# 2-FrontEnd.net
KiCad netlist of a schematic drawn in Altium Designer
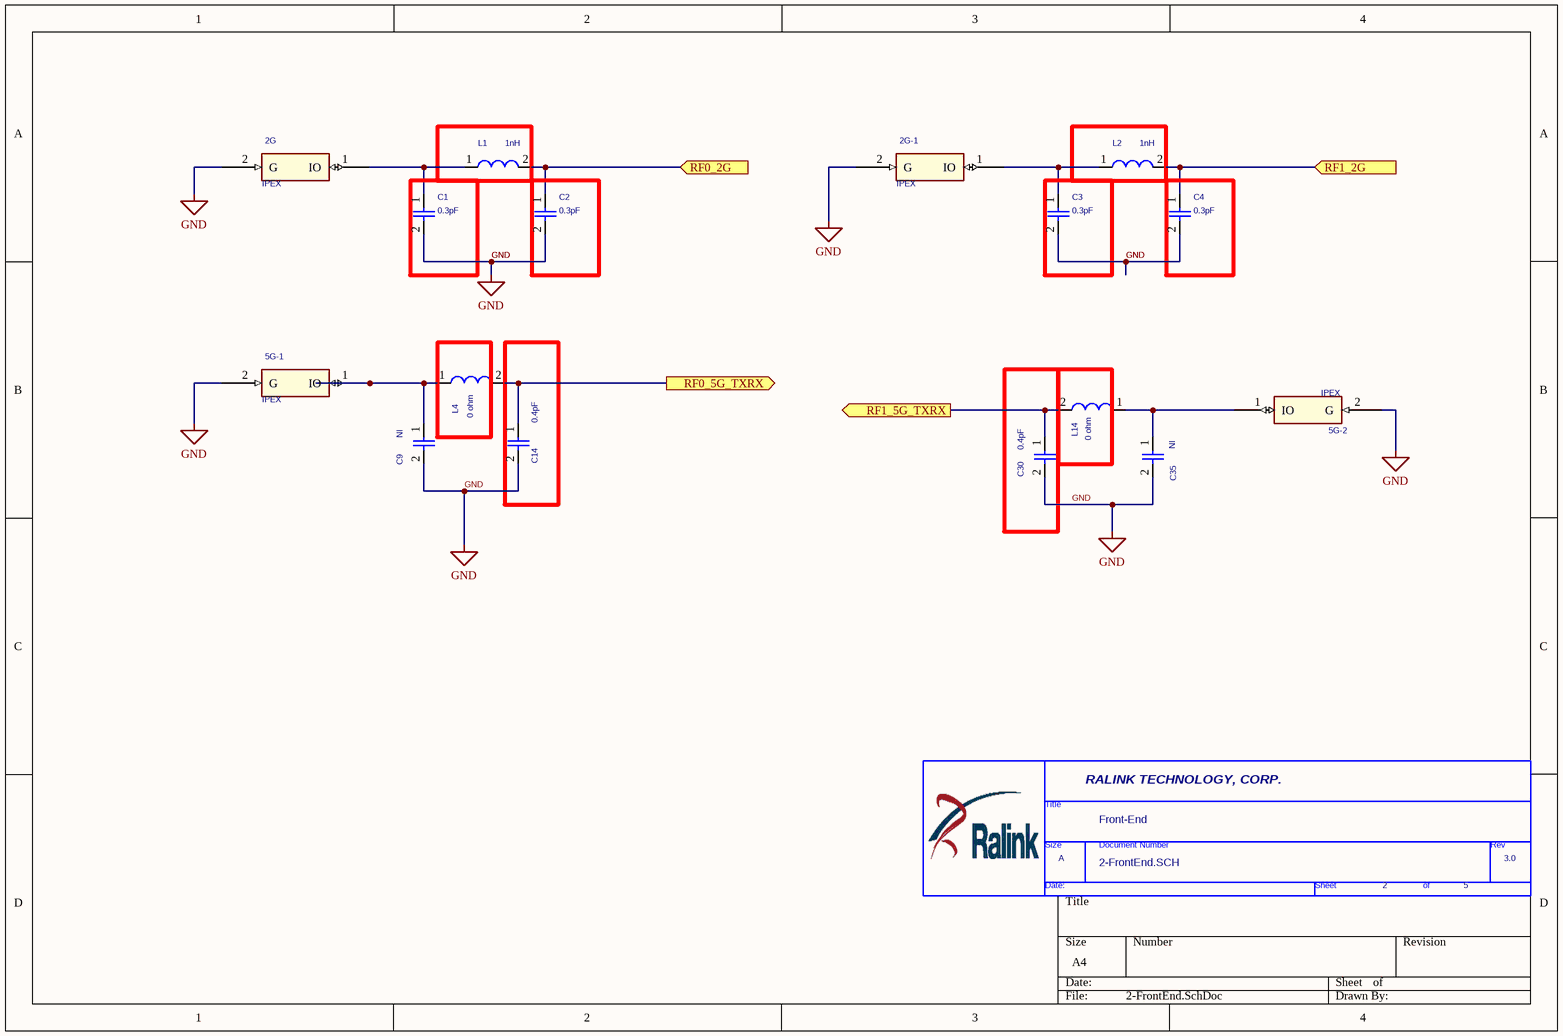
[diagram p0: 2-FrontEnd.SchDoc]

(export (version "E")
  (design (tool "Eeschema 10.0.6"))
  (components
    (comp (ref "2G") (value "IPEX") (footprint "IPEX") (libsource (lib "*") (part "ANT-RA-USB-1")))
    (comp (ref "2G-1") (value "IPEX") (footprint "IPEX") (libsource (lib "*") (part "ANT-RA-USB-1")))
    (comp (ref "5G-1") (value "IPEX") (footprint "IPEX") (libsource (lib "*") (part "ANT-RA-USB-1")))
    (comp (ref "5G-2") (value "IPEX") (footprint "IPEX") (libsource (lib "") (part "ANT-RA-USB-1_1")))
    (comp (ref "C1") (value "0.3pF") (footprint "0402") (libsource (lib "*") (part "CAP/0402")))
    (comp (ref "C2") (value "0.3pF") (footprint "0402") (libsource (lib "*") (part "CAP/0402")))
    (comp (ref "C3") (value "0.3pF") (footprint "0402") (libsource (lib "*") (part "CAP/0402")))
    (comp (ref "C4") (value "0.3pF") (footprint "0402") (libsource (lib "*") (part "CAP/0402")))
    (comp (ref "C9") (value "NI") (footprint "0402") (libsource (lib "*") (part "CAP/0402")))
    (comp (ref "C14") (value "0.4pF") (footprint "0402") (libsource (lib "*") (part "CAP/0402")))
    (comp (ref "C30") (value "0.4pF") (footprint "0402") (libsource (lib "*") (part "CAP/0402")))
    (comp (ref "C35") (value "NI") (footprint "0402") (libsource (lib "*") (part "CAP/0402")))
    (comp (ref "L1") (value "1nH") (footprint "0402") (libsource (lib "*") (part "L/0402")))
    (comp (ref "L2") (value "1nH") (footprint "0402") (libsource (lib "*") (part "L/0402")))
    (comp (ref "L4") (value "0 ohm") (footprint "0402") (libsource (lib "*") (part "L/0402")))
    (comp (ref "L14") (value "0 ohm") (footprint "0402") (libsource (lib "") (part "L/0402_1")))
  )
  (nets
    (net (code "1") (name "/RF0_2G") (class "Default")
      (node (ref "C2") (pin "1") (pinfunction "1_1") (pintype "passive"))
      (node (ref "L1") (pin "2") (pinfunction "2_2") (pintype "passive"))
    )
    (net (code "2") (name "/RF0_5G_TXRX") (class "Default")
      (node (ref "C14") (pin "1") (pinfunction "1_1") (pintype "passive"))
      (node (ref "L4") (pin "2") (pinfunction "2_2") (pintype "passive"))
    )
    (net (code "3") (name "/RF1_2G") (class "Default")
      (node (ref "C4") (pin "1") (pinfunction "1_1") (pintype "passive"))
      (node (ref "L2") (pin "2") (pinfunction "2_2") (pintype "passive"))
    )
    (net (code "4") (name "/RF1_5G_TXRX") (class "Default")
      (node (ref "C30") (pin "1") (pinfunction "1_1") (pintype "passive"))
      (node (ref "L14") (pin "2") (pinfunction "2_2") (pintype "passive"))
    )
    (net (code "5") (name "GND") (class "Default")
      (node (ref "2G") (pin "2") (pinfunction "G_2") (pintype "input"))
      (node (ref "2G-1") (pin "2") (pinfunction "G_2") (pintype "input"))
      (node (ref "5G-1") (pin "2") (pinfunction "G_2") (pintype "input"))
      (node (ref "5G-2") (pin "2") (pinfunction "G_2") (pintype "input"))
      (node (ref "C1") (pin "2") (pinfunction "2_2") (pintype "passive"))
      (node (ref "C14") (pin "2") (pinfunction "2_2") (pintype "passive"))
      (node (ref "C2") (pin "2") (pinfunction "2_2") (pintype "passive"))
      (node (ref "C3") (pin "2") (pinfunction "2_2") (pintype "passive"))
      (node (ref "C30") (pin "2") (pinfunction "2_2") (pintype "passive"))
      (node (ref "C35") (pin "2") (pinfunction "2_2") (pintype "passive"))
      (node (ref "C4") (pin "2") (pinfunction "2_2") (pintype "passive"))
      (node (ref "C9") (pin "2") (pinfunction "2_2") (pintype "passive"))
    )
    (net (code "6") (name "Net-(2G-1-IO)") (class "Default")
      (node (ref "2G-1") (pin "1") (pinfunction "IO_1") (pintype "bidirectional"))
      (node (ref "C3") (pin "1") (pinfunction "1_1") (pintype "passive"))
      (node (ref "L2") (pin "1") (pinfunction "1_1") (pintype "passive"))
    )
    (net (code "7") (name "Net-(2G-IO)") (class "Default")
      (node (ref "2G") (pin "1") (pinfunction "IO_1") (pintype "bidirectional"))
      (node (ref "C1") (pin "1") (pinfunction "1_1") (pintype "passive"))
      (node (ref "L1") (pin "1") (pinfunction "1_1") (pintype "passive"))
    )
    (net (code "8") (name "Net-(5G-1-IO)") (class "Default")
      (node (ref "5G-1") (pin "1") (pinfunction "IO_1") (pintype "bidirectional"))
      (node (ref "C9") (pin "1") (pinfunction "1_1") (pintype "passive"))
      (node (ref "L4") (pin "1") (pinfunction "1_1") (pintype "passive"))
    )
    (net (code "9") (name "Net-(5G-2-IO)") (class "Default")
      (node (ref "5G-2") (pin "1") (pinfunction "IO_1") (pintype "bidirectional"))
      (node (ref "C35") (pin "1") (pinfunction "1_1") (pintype "passive"))
      (node (ref "L14") (pin "1") (pinfunction "1_1") (pintype "passive"))
    )
  )
)
